# yetis_lsb_v1_7_2.net
KiCad netlist of a schematic drawn in EAGLE
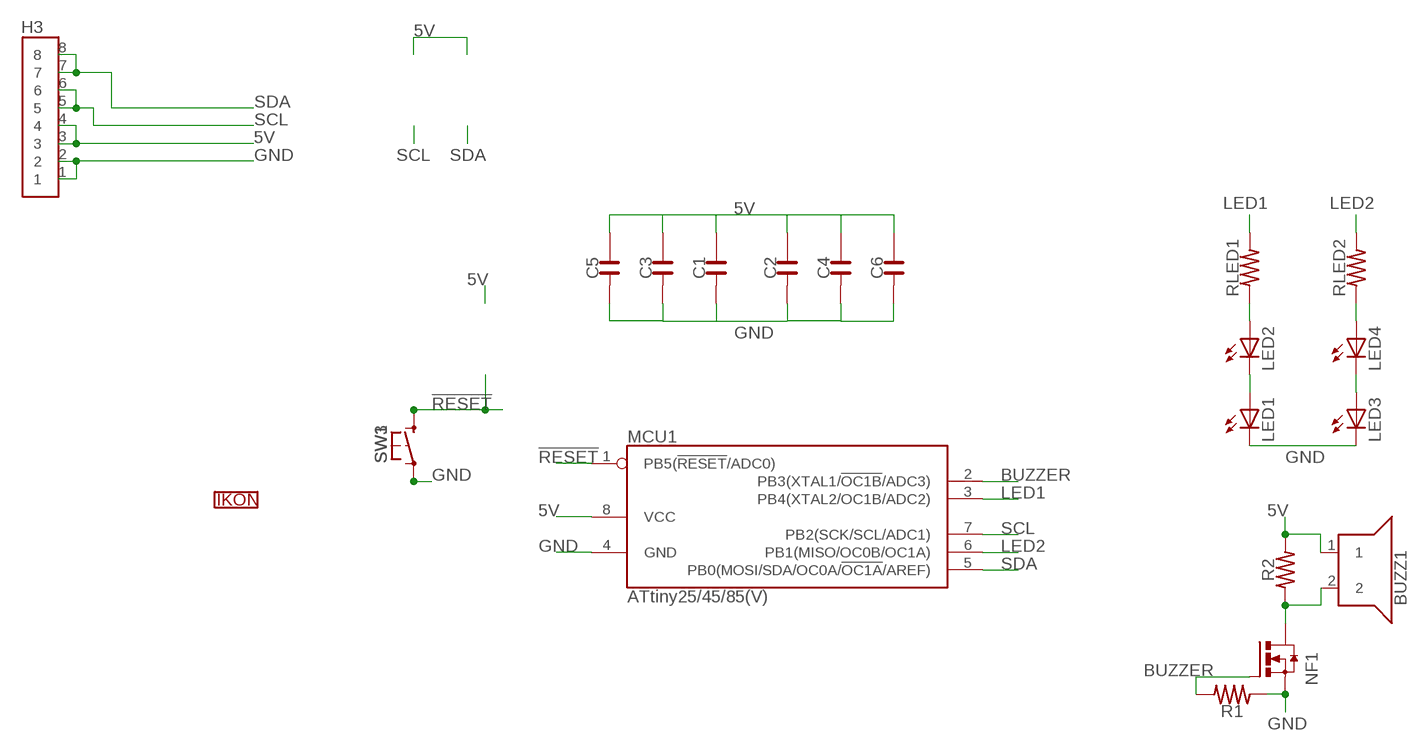
[diagram p0: schematic, sheet 1]

(export (version "E")
  (design (tool "Eeschema 10.0.6"))
  (components
    (comp (ref "BUZZ1")
      (value "BUZZER-PS1240P02BT")
      (footprint "eagle-import:BUZZ_PS1240P02BT")
      (libsource (lib "eagle-import") (part "BUZZER-PS1240P02BT"))
    )
    (comp (ref "C1")
      (value "CAPACITOR-1206")
      (footprint "eagle-import:1206_YAGEO")
      (libsource (lib "eagle-import") (part "CAPACITOR-1206"))
    )
    (comp (ref "C2")
      (value "CAPACITOR-1206")
      (footprint "eagle-import:1206_YAGEO")
      (libsource (lib "eagle-import") (part "CAPACITOR-1206"))
    )
    (comp (ref "C3")
      (value "CAPACITOR-0805")
      (footprint "eagle-import:0805_YAGEO")
      (libsource (lib "eagle-import") (part "CAPACITOR-0805"))
    )
    (comp (ref "C4")
      (value "CAPACITOR-0805")
      (footprint "eagle-import:0805_YAGEO")
      (libsource (lib "eagle-import") (part "CAPACITOR-0805"))
    )
    (comp (ref "C5")
      (value "CAPACITOR-0603")
      (footprint "eagle-import:0603_YAGEO")
      (libsource (lib "eagle-import") (part "CAPACITOR-0603"))
    )
    (comp (ref "C6")
      (value "CAPACITOR-0603")
      (footprint "eagle-import:0603_YAGEO")
      (libsource (lib "eagle-import") (part "CAPACITOR-0603"))
    )
    (comp (ref "H3")
      (value "HEADER_8P-0.1\"_2X4-SMD-SULLINS")
      (footprint "eagle-import:HEADER-0.1__2X4-SMD-SULLINS")
      (libsource (lib "eagle-import") (part "HEADER_8P-0.1{dblquote}_2X4-SMD-SULLINS"))
    )
    (comp (ref "LED1")
      (value "LED-7.62MM-PTH")
      (footprint "eagle-import:7.6MM_LED_PTH")
      (libsource (lib "eagle-import") (part "LED-7.62MM-PTH"))
    )
    (comp (ref "LED2")
      (value "LED-7.62MM-PTH")
      (footprint "eagle-import:7.6MM_LED_PTH")
      (libsource (lib "eagle-import") (part "LED-7.62MM-PTH"))
    )
    (comp (ref "LED3")
      (value "LED-7.62MM-PTH")
      (footprint "eagle-import:7.6MM_LED_PTH")
      (libsource (lib "eagle-import") (part "LED-7.62MM-PTH"))
    )
    (comp (ref "LED4")
      (value "LED-7.62MM-PTH")
      (footprint "eagle-import:7.6MM_LED_PTH")
      (libsource (lib "eagle-import") (part "LED-7.62MM-PTH"))
    )
    (comp (ref "MCU1")
      (value "ATMEL_ATTINY25/45/85(V)-SOIC_DUAL")
      (footprint "eagle-import:SOIC-8_DUAL")
      (libsource (lib "eagle-import") (part "ATMEL_ATTINY25/45/85(V)-SOIC_DUAL"))
    )
    (comp (ref "NF1")
      (value "FET_N-CH-SOT-23-3-LITTLEFOOT")
      (footprint "eagle-import:SOT-23-3-LITTLEFOOT")
      (libsource (lib "eagle-import") (part "FET_N-CH-SOT-23-3-LITTLEFOOT"))
    )
    (comp (ref "R1")
      (value "RESISTOR-0603")
      (footprint "eagle-import:0603_YAGEO")
      (libsource (lib "eagle-import") (part "RESISTOR-0603"))
    )
    (comp (ref "R2")
      (value "RESISTOR-0603")
      (footprint "eagle-import:0603_YAGEO")
      (libsource (lib "eagle-import") (part "RESISTOR-0603"))
    )
    (comp (ref "RLED1")
      (value "RESISTOR-0603")
      (footprint "eagle-import:0603_YAGEO")
      (libsource (lib "eagle-import") (part "RESISTOR-0603"))
    )
    (comp (ref "RLED2")
      (value "RESISTOR-0603")
      (footprint "eagle-import:0603_YAGEO")
      (libsource (lib "eagle-import") (part "RESISTOR-0603"))
    )
    (comp (ref "SW1")
      (value "SWITCH_SPST-KMT0")
      (footprint "eagle-import:SWITCH_KMT0")
      (libsource (lib "eagle-import") (part "SWITCH_SPST-KMT0"))
    )
    (comp (ref "SW3")
      (value "SWITCH_SPST-TL3315")
      (footprint "eagle-import:SWITCH_TL3315")
      (libsource (lib "eagle-import") (part "SWITCH_SPST-TL3315"))
    )
    (comp (ref "U$11")
      (value "IKONLEARNING-20MIL")
      (footprint "eagle-import:IKON_LEARNING_20MIL")
      (libsource (lib "eagle-import") (part "IKONLEARNING-20MIL"))
    )
  )
  (nets
    (net (code "1") (name "/5V") (class "Default")
      (node (ref "BUZZ1") (pin "1") (pinfunction "1_1") (pintype "bidirectional"))
      (node (ref "C1") (pin "2") (pinfunction "P$2_2") (pintype "passive"))
      (node (ref "C2") (pin "2") (pinfunction "P$2_2") (pintype "passive"))
      (node (ref "C3") (pin "2") (pinfunction "P$2_2") (pintype "passive"))
      (node (ref "C4") (pin "2") (pinfunction "P$2_2") (pintype "passive"))
      (node (ref "C5") (pin "2") (pinfunction "P$2_2") (pintype "passive"))
      (node (ref "C6") (pin "2") (pinfunction "P$2_2") (pintype "passive"))
      (node (ref "H3") (pin "3") (pinfunction "3_3") (pintype "bidirectional"))
      (node (ref "H3") (pin "4") (pinfunction "4_4") (pintype "bidirectional"))
      (node (ref "MCU1") (pin "8") (pinfunction "VCC_8") (pintype "bidirectional"))
      (node (ref "R2") (pin "2") (pinfunction "2_2") (pintype "passive"))
    )
    (net (code "2") (name "/BUZZER") (class "Default")
      (node (ref "MCU1") (pin "2") (pinfunction "PB3(XTAL1/~{OC1B}/ADC3)_2") (pintype "bidirectional"))
      (node (ref "NF1") (pin "G") (pinfunction "G_G") (pintype "passive"))
      (node (ref "R1") (pin "2") (pinfunction "2_2") (pintype "passive"))
    )
    (net (code "3") (name "/GND") (class "Default")
      (node (ref "C1") (pin "1") (pinfunction "P$1_1") (pintype "passive"))
      (node (ref "C2") (pin "1") (pinfunction "P$1_1") (pintype "passive"))
      (node (ref "C3") (pin "1") (pinfunction "P$1_1") (pintype "passive"))
      (node (ref "C4") (pin "1") (pinfunction "P$1_1") (pintype "passive"))
      (node (ref "C5") (pin "1") (pinfunction "P$1_1") (pintype "passive"))
      (node (ref "C6") (pin "1") (pinfunction "P$1_1") (pintype "passive"))
      (node (ref "H3") (pin "1") (pinfunction "1_1") (pintype "bidirectional"))
      (node (ref "H3") (pin "2") (pinfunction "2_2") (pintype "bidirectional"))
      (node (ref "LED1") (pin "1") (pinfunction "C_1") (pintype "passive"))
      (node (ref "LED1") (pin "2") (pinfunction "C_2") (pintype "passive"))
      (node (ref "LED3") (pin "1") (pinfunction "C_1") (pintype "passive"))
      (node (ref "LED3") (pin "2") (pinfunction "C_2") (pintype "passive"))
      (node (ref "MCU1") (pin "4") (pinfunction "GND_4") (pintype "bidirectional"))
      (node (ref "NF1") (pin "S@0") (pinfunction "S_S@0") (pintype "passive"))
      (node (ref "R1") (pin "1") (pinfunction "1_1") (pintype "passive"))
      (node (ref "SW1") (pin "2@1") (pinfunction "2_2@1") (pintype "passive"))
      (node (ref "SW1") (pin "2@2") (pinfunction "2_2@2") (pintype "passive"))
      (node (ref "SW3") (pin "2@1") (pinfunction "2_2@1") (pintype "passive"))
      (node (ref "SW3") (pin "2@2") (pinfunction "2_2@2") (pintype "passive"))
    )
    (net (code "4") (name "/LED1") (class "Default")
      (node (ref "MCU1") (pin "3") (pinfunction "PB4(XTAL2/OC1B/ADC2)_3") (pintype "bidirectional"))
      (node (ref "RLED1") (pin "2") (pinfunction "2_2") (pintype "passive"))
    )
    (net (code "5") (name "/LED2") (class "Default")
      (node (ref "MCU1") (pin "6") (pinfunction "PB1(MISO/OC0B/OC1A)_6") (pintype "bidirectional"))
      (node (ref "RLED2") (pin "2") (pinfunction "2_2") (pintype "passive"))
    )
    (net (code "6") (name "/SCL") (class "Default")
      (node (ref "H3") (pin "5") (pinfunction "5_5") (pintype "bidirectional"))
      (node (ref "H3") (pin "6") (pinfunction "6_6") (pintype "bidirectional"))
      (node (ref "MCU1") (pin "7") (pinfunction "PB2(SCK/SCL/ADC1)_7") (pintype "bidirectional"))
    )
    (net (code "7") (name "/SDA") (class "Default")
      (node (ref "H3") (pin "7") (pinfunction "7_7") (pintype "bidirectional"))
      (node (ref "H3") (pin "8") (pinfunction "8_8") (pintype "bidirectional"))
      (node (ref "MCU1") (pin "5") (pinfunction "PB0(MOSI/SDA/OC0A/~{OC1A}/AREF)_5") (pintype "bidirectional"))
    )
    (net (code "8") (name "/~{RESET}") (class "Default")
      (node (ref "MCU1") (pin "1") (pinfunction "PB5(~{RESET}/ADC0)_1") (pintype "bidirectional"))
      (node (ref "SW1") (pin "1@1") (pinfunction "1_1@1") (pintype "passive"))
      (node (ref "SW1") (pin "1@2") (pinfunction "1_1@2") (pintype "passive"))
      (node (ref "SW3") (pin "1@1") (pinfunction "1_1@1") (pintype "passive"))
      (node (ref "SW3") (pin "1@2") (pinfunction "1_1@2") (pintype "passive"))
    )
    (net (code "9") (name "Net-(LED1-A-Pad3)") (class "Default")
      (node (ref "LED1") (pin "3") (pinfunction "A_3") (pintype "passive"))
      (node (ref "LED1") (pin "4") (pinfunction "A_4") (pintype "passive"))
      (node (ref "LED2") (pin "1") (pinfunction "C_1") (pintype "passive"))
      (node (ref "LED2") (pin "2") (pinfunction "C_2") (pintype "passive"))
    )
    (net (code "10") (name "Net-(LED2-A-Pad3)") (class "Default")
      (node (ref "LED2") (pin "3") (pinfunction "A_3") (pintype "passive"))
      (node (ref "LED2") (pin "4") (pinfunction "A_4") (pintype "passive"))
      (node (ref "RLED1") (pin "1") (pinfunction "1_1") (pintype "passive"))
    )
    (net (code "11") (name "Net-(LED3-A-Pad3)") (class "Default")
      (node (ref "LED3") (pin "3") (pinfunction "A_3") (pintype "passive"))
      (node (ref "LED3") (pin "4") (pinfunction "A_4") (pintype "passive"))
      (node (ref "LED4") (pin "1") (pinfunction "C_1") (pintype "passive"))
      (node (ref "LED4") (pin "2") (pinfunction "C_2") (pintype "passive"))
    )
    (net (code "12") (name "Net-(LED4-A-Pad3)") (class "Default")
      (node (ref "LED4") (pin "3") (pinfunction "A_3") (pintype "passive"))
      (node (ref "LED4") (pin "4") (pinfunction "A_4") (pintype "passive"))
      (node (ref "RLED2") (pin "1") (pinfunction "1_1") (pintype "passive"))
    )
    (net (code "13") (name "Net-(NF1-D)") (class "Default")
      (node (ref "BUZZ1") (pin "2") (pinfunction "2_2") (pintype "bidirectional"))
      (node (ref "NF1") (pin "D@0") (pinfunction "D_D@0") (pintype "passive"))
      (node (ref "R2") (pin "1") (pinfunction "1_1") (pintype "passive"))
    )
  )
)
